# I2C_Keypad_host_module.net
KiCad netlist of a schematic drawn in Altium Designer
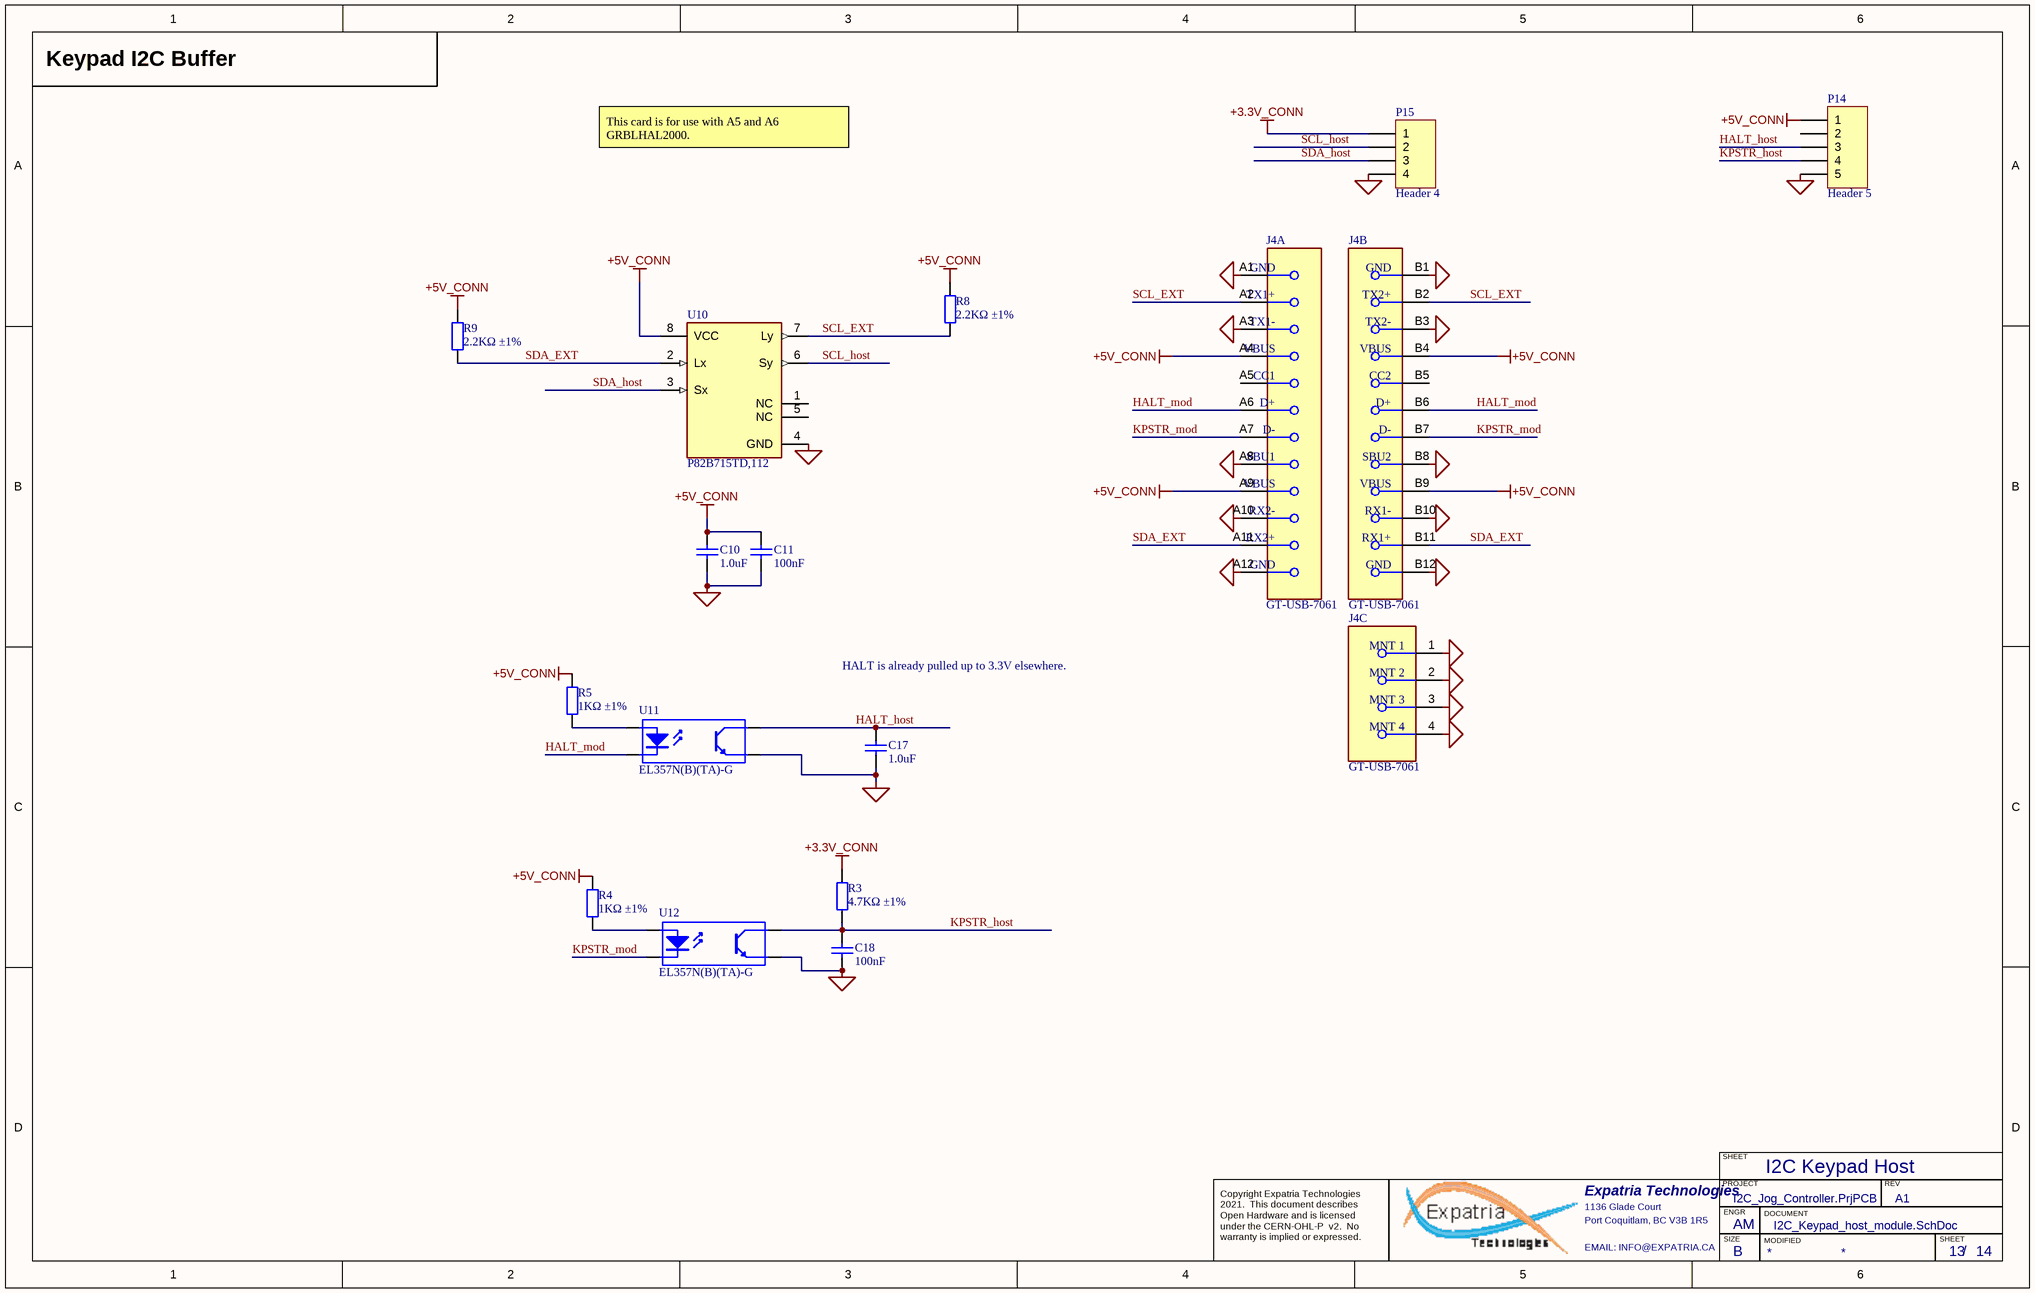
[diagram p0: I2C_Keypad_host_module.SchDoc]

(export (version "E")
  (design (tool "Eeschema 10.0.6"))
  (components
    (comp (ref "C10")
      (value "1.0uF")
      (footprint "0402_C")
      (description "Chip capacitor")
      (fields
        (field (name "MANUFACTURER") "Samsung Electro-Mechanics")
        (field (name "PARTNUMBER") "CL05A105KA5NQNC")
      )
      (libsource (lib "Cap") (part "0402 1.0uF (105) 10% 25V"))
    )
    (comp (ref "C11")
      (value "100nF")
      (footprint "0402_C")
      (description "Chip capacitors")
      (fields
        (field (name "MANUFACTURER") "Samsung Electro-Mechanics")
        (field (name "PARTNUMBER") "CL05B104KO5NNNC")
      )
      (libsource (lib "Cap") (part "0402 100nF (104) 10% 16V"))
    )
    (comp (ref "C17")
      (value "1.0uF")
      (footprint "0402_C")
      (description "Chip capacitor")
      (fields
        (field (name "MANUFACTURER") "Samsung Electro-Mechanics")
        (field (name "PARTNUMBER") "CL05A105KA5NQNC")
      )
      (libsource (lib "Cap") (part "0402 1.0uF (105) 10% 25V"))
    )
    (comp (ref "C18")
      (value "100nF")
      (footprint "0402_C")
      (description "Chip capacitors")
      (fields
        (field (name "MANUFACTURER") "Samsung Electro-Mechanics")
        (field (name "PARTNUMBER") "CL05B104KO5NNNC")
      )
      (libsource (lib "Cap") (part "0402 100nF (104) 10% 16V"))
    )
    (comp (ref "J4")
      (value "GT-USB-7061")
      (footprint "USB-C-SMD_GT-USB-7061")
      (description "CONN RCP USB3.1 TYPEC 24P SMD VERT")
      (fields (field (name "MANUFACTURER") "G-Switch"))
      (libsource (lib "I2C_Jog_Controller") (part "USBC-GT-USB-7061"))
    )
    (comp (ref "P14")
      (value "Header 5")
      (footprint "HDR1X5")
      (description "Header, 5-Pin")
      (fields (field (name "PUBLISHER") "Altium Limited"))
      (libsource (lib "PrintNC_GRBLHAL_Breakout") (part "Header 5"))
    )
    (comp (ref "P15")
      (value "Header 4")
      (footprint "HDR1X4")
      (description "Header, 4-Pin")
      (fields (field (name "PUBLISHER") "Altium Limited"))
      (libsource (lib "PrintNC_GRBLHAL_Breakout") (part "Header 4"))
    )
    (comp (ref "R3")
      (value "4.7KΩ ±1%")
      (footprint "0402_R")
      (description "Chip resistor")
      (fields (field (name "MANUFACTURER") "Uniroyal Elec") (field (name "PARTNUMBER") "0402WGF4701TCE"))
      (libsource (lib "RES") (part "0402 4.7K (4701) 1%"))
    )
    (comp (ref "R4")
      (value "1KΩ ±1%")
      (footprint "0402_R")
      (description "Chip resistor")
      (fields (field (name "MANUFACTURER") "Uniroyal Elec") (field (name "PARTNUMBER") "0402WGF1001TCE"))
      (libsource (lib "RES") (part "0402 1K (1001) 1%"))
    )
    (comp (ref "R5")
      (value "1KΩ ±1%")
      (footprint "0402_R")
      (description "Chip resistor")
      (fields (field (name "MANUFACTURER") "Uniroyal Elec") (field (name "PARTNUMBER") "0402WGF1001TCE"))
      (libsource (lib "RES") (part "0402 1K (1001) 1%"))
    )
    (comp (ref "R8")
      (value "2.2KΩ ±1%")
      (footprint "0402_R")
      (description "Chip resistor")
      (fields (field (name "MANUFACTURER") "Uniroyal Elec") (field (name "PARTNUMBER") "0402WGF2201TCE"))
      (libsource (lib "PrintNC_GRBLHAL_Breakout") (part "0402 2.2K (2201) 1%"))
    )
    (comp (ref "R9")
      (value "2.2KΩ ±1%")
      (footprint "0402_R")
      (description "Chip resistor")
      (fields (field (name "MANUFACTURER") "Uniroyal Elec") (field (name "PARTNUMBER") "0402WGF2201TCE"))
      (libsource (lib "") (part "0402 2.2K (2201) 1%_1"))
    )
    (comp (ref "U10")
      (value "P82B715TD,112")
      (footprint "FP-SOT96-1-MFG")
      (description "IC REDRIVER I2C 1CH 400KHZ 8SO")
      (fields
        (field (name "MANUFACTURER") "NXP Semicon")
        (field (name "MANUFACTURER_PART_NUMBER") "P82B715TD,118")
      )
      (libsource (lib "Altium Content Vault") (part "feec727f4072afc4f94d4e12e138974"))
    )
    (comp (ref "U11")
      (value "EL357N(B)(TA)-G")
      (footprint "SOP-4_P2.54")
      (description "贴片光耦")
      (libsource (lib "IC") (part "EL357N(B)(TA)-G_[C6649]"))
    )
    (comp (ref "U12")
      (value "EL357N(B)(TA)-G")
      (footprint "SOP-4_P2.54")
      (description "贴片光耦")
      (libsource (lib "IC") (part "EL357N(B)(TA)-G_[C6649]"))
    )
  )
  (nets
    (net (code "1") (name "+3.3V_CONN") (class "Default")
      (node (ref "P15") (pin "1") (pinfunction "1_1") (pintype "passive"))
      (node (ref "R3") (pin "2") (pinfunction "2_2") (pintype "passive"))
    )
    (net (code "2") (name "+5V_CONN") (class "Default")
      (node (ref "C10") (pin "2") (pinfunction "2_2") (pintype "passive"))
      (node (ref "C11") (pin "2") (pinfunction "2_2") (pintype "passive"))
      (node (ref "J4") (pin "A4") (pinfunction "VBUS_A4") (pintype "passive"))
      (node (ref "J4") (pin "A9") (pinfunction "VBUS_A9") (pintype "passive"))
      (node (ref "J4") (pin "B4") (pinfunction "VBUS_B4") (pintype "passive"))
      (node (ref "J4") (pin "B9") (pinfunction "VBUS_B9") (pintype "passive"))
      (node (ref "P14") (pin "1") (pinfunction "1_1") (pintype "passive"))
      (node (ref "R4") (pin "1") (pinfunction "1_1") (pintype "passive"))
      (node (ref "R5") (pin "1") (pinfunction "1_1") (pintype "passive"))
      (node (ref "R8") (pin "2") (pinfunction "2_2") (pintype "passive"))
      (node (ref "R9") (pin "2") (pinfunction "2_2") (pintype "passive"))
      (node (ref "U10") (pin "8") (pinfunction "VCC_8") (pintype "power_in"))
    )
    (net (code "3") (name "/HALT_host") (class "Default")
      (node (ref "C17") (pin "2") (pinfunction "2_2") (pintype "passive"))
      (node (ref "P14") (pin "3") (pinfunction "3_3") (pintype "passive"))
      (node (ref "U11") (pin "4") (pinfunction "C_4") (pintype "passive"))
    )
    (net (code "4") (name "/HALT_mod") (class "Default")
      (node (ref "J4") (pin "A6") (pinfunction "D+_A6") (pintype "passive"))
      (node (ref "J4") (pin "B6") (pinfunction "D+_B6") (pintype "passive"))
      (node (ref "U11") (pin "2") (pinfunction "K_2") (pintype "passive"))
    )
    (net (code "5") (name "/KPSTR_host") (class "Default")
      (node (ref "C18") (pin "2") (pinfunction "2_2") (pintype "passive"))
      (node (ref "P14") (pin "4") (pinfunction "4_4") (pintype "passive"))
      (node (ref "R3") (pin "1") (pinfunction "1_1") (pintype "passive"))
      (node (ref "U12") (pin "4") (pinfunction "C_4") (pintype "passive"))
    )
    (net (code "6") (name "/KPSTR_mod") (class "Default")
      (node (ref "J4") (pin "A7") (pinfunction "D-_A7") (pintype "passive"))
      (node (ref "J4") (pin "B7") (pinfunction "D-_B7") (pintype "passive"))
      (node (ref "U12") (pin "2") (pinfunction "K_2") (pintype "passive"))
    )
    (net (code "7") (name "/SCL_EXT") (class "Default")
      (node (ref "J4") (pin "A2") (pinfunction "TX1+_A2") (pintype "passive"))
      (node (ref "J4") (pin "B2") (pinfunction "TX2+_B2") (pintype "passive"))
      (node (ref "R8") (pin "1") (pinfunction "1_1") (pintype "passive"))
      (node (ref "U10") (pin "7") (pinfunction "Ly_7") (pintype "output"))
    )
    (net (code "8") (name "/SCL_host") (class "Default")
      (node (ref "P15") (pin "2") (pinfunction "2_2") (pintype "passive"))
      (node (ref "U10") (pin "6") (pinfunction "Sy_6") (pintype "output"))
    )
    (net (code "9") (name "/SDA_EXT") (class "Default")
      (node (ref "J4") (pin "A11") (pinfunction "RX2+_A11") (pintype "passive"))
      (node (ref "J4") (pin "B11") (pinfunction "RX1+_B11") (pintype "passive"))
      (node (ref "R9") (pin "1") (pinfunction "1_1") (pintype "passive"))
      (node (ref "U10") (pin "2") (pinfunction "Lx_2") (pintype "input"))
    )
    (net (code "10") (name "/SDA_host") (class "Default")
      (node (ref "P15") (pin "3") (pinfunction "3_3") (pintype "passive"))
      (node (ref "U10") (pin "3") (pinfunction "Sx_3") (pintype "input"))
    )
    (net (code "11") (name "GND_CONN") (class "Default")
      (node (ref "C10") (pin "1") (pinfunction "1_1") (pintype "passive"))
      (node (ref "C11") (pin "1") (pinfunction "1_1") (pintype "passive"))
      (node (ref "C17") (pin "1") (pinfunction "1_1") (pintype "passive"))
      (node (ref "C18") (pin "1") (pinfunction "1_1") (pintype "passive"))
      (node (ref "J4") (pin "1") (pinfunction "MNT_1_1") (pintype "passive"))
      (node (ref "J4") (pin "2") (pinfunction "MNT_2_2") (pintype "passive"))
      (node (ref "J4") (pin "3") (pinfunction "MNT_3_3") (pintype "passive"))
      (node (ref "J4") (pin "4") (pinfunction "MNT_4_4") (pintype "passive"))
      (node (ref "J4") (pin "A1") (pinfunction "GND_A1") (pintype "passive"))
      (node (ref "J4") (pin "A10") (pinfunction "RX2-_A10") (pintype "passive"))
      (node (ref "J4") (pin "A12") (pinfunction "GND_A12") (pintype "passive"))
      (node (ref "J4") (pin "A3") (pinfunction "TX1-_A3") (pintype "passive"))
      (node (ref "J4") (pin "A8") (pinfunction "SBU1_A8") (pintype "passive"))
      (node (ref "J4") (pin "B1") (pinfunction "GND_B1") (pintype "passive"))
      (node (ref "J4") (pin "B10") (pinfunction "RX1-_B10") (pintype "passive"))
      (node (ref "J4") (pin "B12") (pinfunction "GND_B12") (pintype "passive"))
      (node (ref "J4") (pin "B3") (pinfunction "TX2-_B3") (pintype "passive"))
      (node (ref "J4") (pin "B8") (pinfunction "SBU2_B8") (pintype "passive"))
      (node (ref "P14") (pin "5") (pinfunction "5_5") (pintype "passive"))
      (node (ref "P15") (pin "4") (pinfunction "4_4") (pintype "passive"))
      (node (ref "U10") (pin "4") (pinfunction "GND_4") (pintype "power_in"))
      (node (ref "U11") (pin "3") (pinfunction "E_3") (pintype "passive"))
      (node (ref "U12") (pin "3") (pinfunction "E_3") (pintype "passive"))
    )
    (net (code "12") (name "Net-(U11-A)") (class "Default")
      (node (ref "R5") (pin "2") (pinfunction "2_2") (pintype "passive"))
      (node (ref "U11") (pin "1") (pinfunction "A_1") (pintype "passive"))
    )
    (net (code "13") (name "Net-(U12-A)") (class "Default")
      (node (ref "R4") (pin "2") (pinfunction "2_2") (pintype "passive"))
      (node (ref "U12") (pin "1") (pinfunction "A_1") (pintype "passive"))
    )
    (net (code "14") (name "unconnected-(J4A-CC1-PadA5)") (class "Default")
      (node (ref "J4") (pin "A5") (pinfunction "CC1_A5") (pintype "passive"))
    )
    (net (code "15") (name "unconnected-(J4B-CC2-PadB5)") (class "Default")
      (node (ref "J4") (pin "B5") (pinfunction "CC2_B5") (pintype "passive"))
    )
    (net (code "16") (name "unconnected-(P14-Pad2)") (class "Default")
      (node (ref "P14") (pin "2") (pinfunction "2_2") (pintype "passive"))
    )
    (net (code "17") (name "unconnected-(U10-NC-Pad1)") (class "Default")
      (node (ref "U10") (pin "1") (pinfunction "NC_1") (pintype "passive"))
    )
    (net (code "18") (name "unconnected-(U10-NC-Pad5)") (class "Default")
      (node (ref "U10") (pin "5") (pinfunction "NC_5") (pintype "passive"))
    )
  )
)
